# Voltage_Divider.net
KiCad netlist of a schematic drawn in Altium Designer
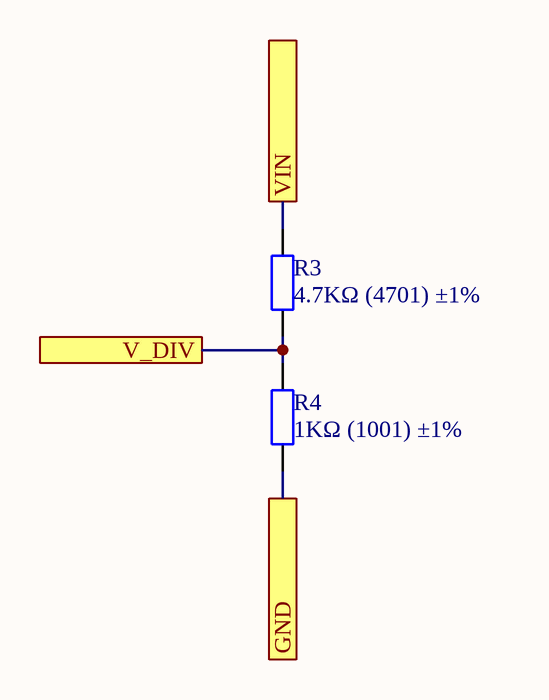
[diagram p0: Voltage_Divider.SchDoc]

(export (version "E")
  (design (tool "Eeschema 10.0.6"))
  (components
    (comp (ref "R3")
      (value "4.7KΩ (4701) ±1%")
      (footprint "0805_R")
      (description "贴片电阻")
      (libsource (lib "Miscellaneous Devices LC") (part "0805 4.7KΩ (4701) 1%"))
    )
    (comp (ref "R4")
      (value "1KΩ (1001) ±1%")
      (footprint "0805_R")
      (description "贴片电阻")
      (libsource (lib "Miscellaneous Devices LC") (part "0805 1KΩ (1001) 1%"))
    )
  )
  (nets
    (net (code "1") (name "/GND") (class "Default")
      (node (ref "R4") (pin "1") (pinfunction "1_1") (pintype "passive"))
    )
    (net (code "2") (name "/VIN") (class "Default")
      (node (ref "R3") (pin "2") (pinfunction "2_2") (pintype "passive"))
    )
    (net (code "3") (name "/V_DIV") (class "Default")
      (node (ref "R3") (pin "1") (pinfunction "1_1") (pintype "passive"))
      (node (ref "R4") (pin "2") (pinfunction "2_2") (pintype "passive"))
    )
  )
)
